# Agit_POVera_rev_3.net
KiCad netlist of a schematic drawn in EAGLE
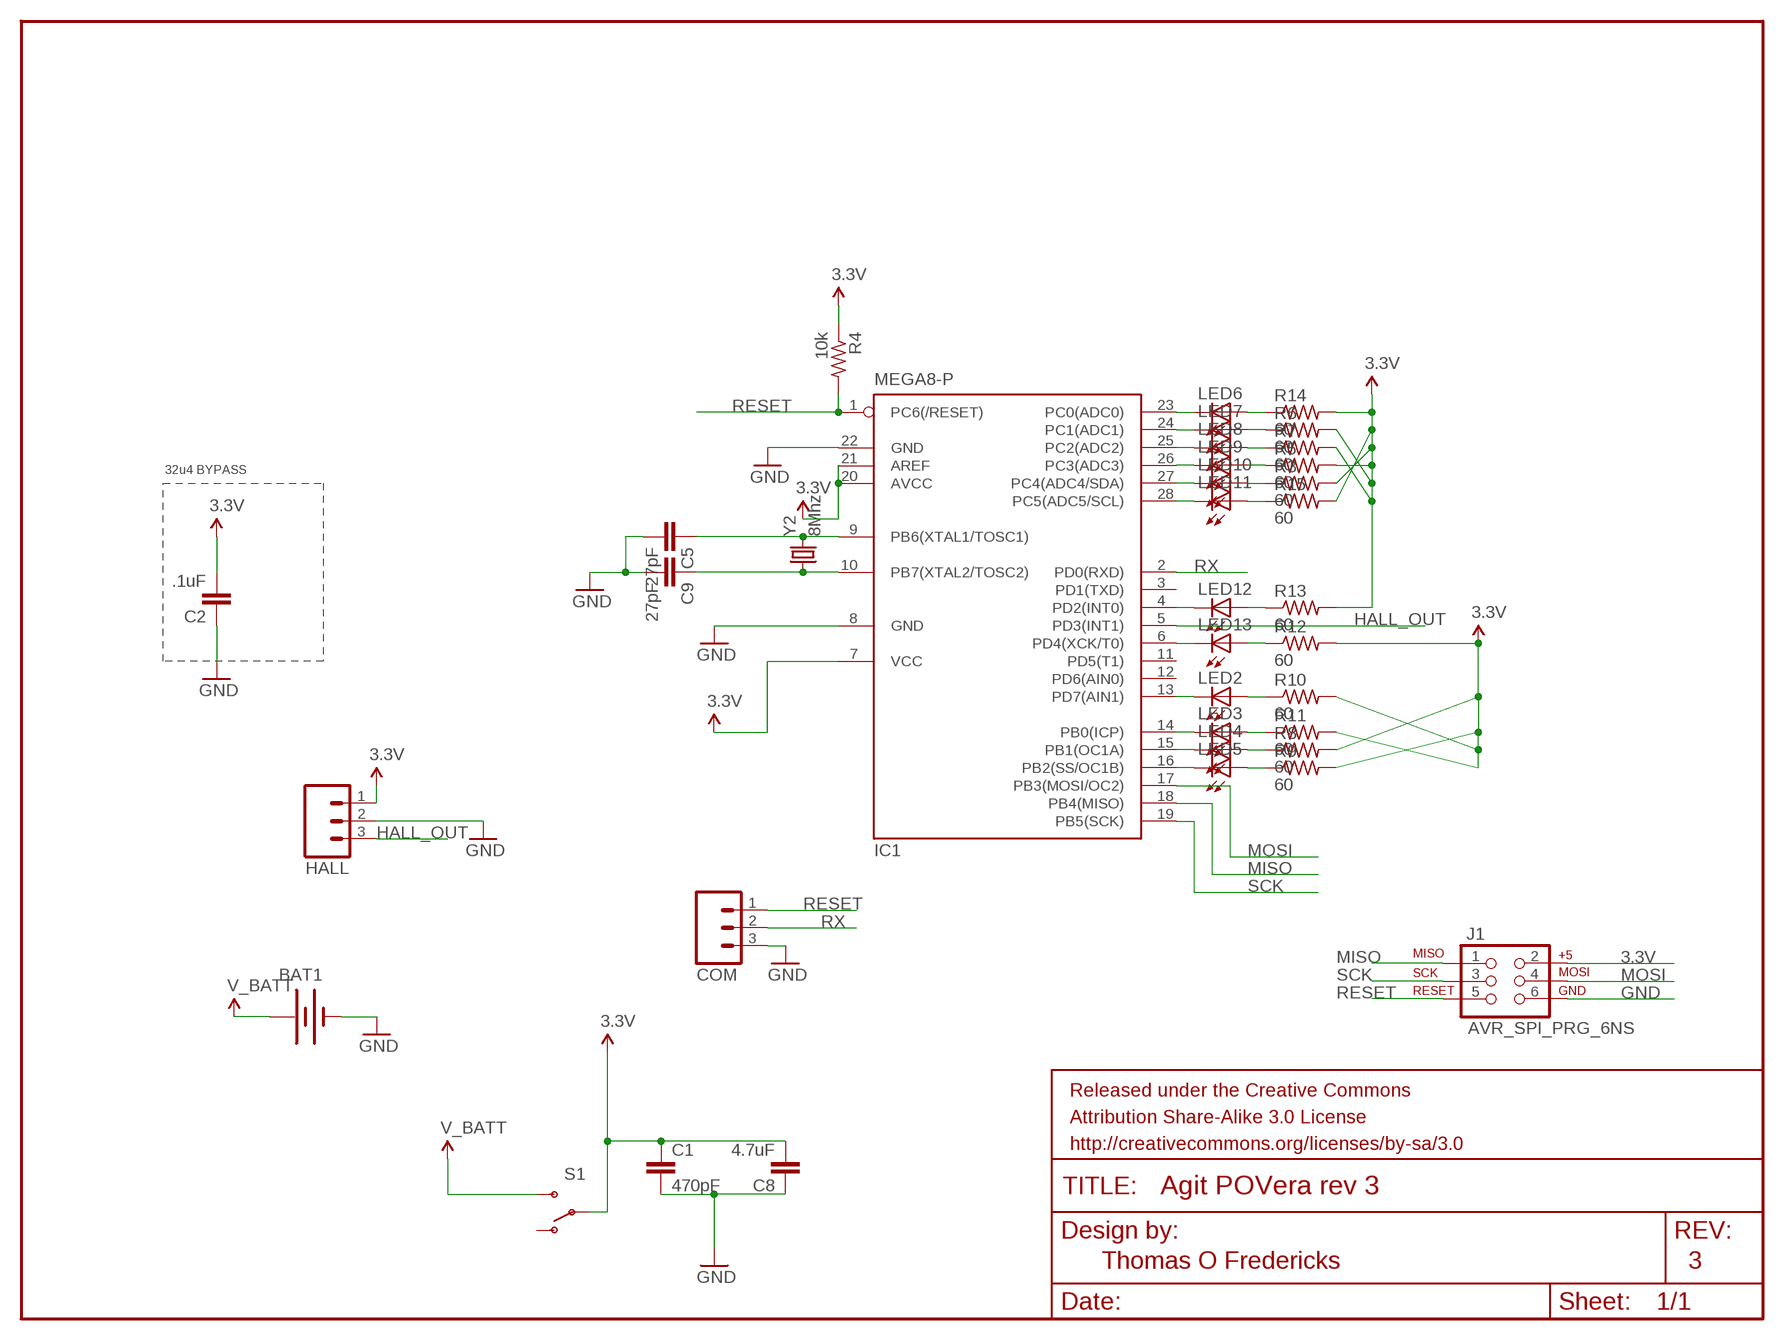
[diagram p0: schematic, sheet 1]

(export (version "E")
  (design (tool "Eeschema 10.0.6"))
  (components
    (comp (ref "BAT1")
      (value "BATTERY20PTH")
      (footprint "eagle-import:BATTCOM_20MM_PTH")
      (libsource (lib "eagle-import") (part "BATTERY20PTH"))
    )
    (comp (ref "C1")
      (value "470pF")
      (footprint "eagle-import:CAP-PTH-SMALLEZ")
      (libsource (lib "eagle-import") (part "CAPEZ"))
    )
    (comp (ref "C2")
      (value ".1uF")
      (footprint "eagle-import:CAP-PTH-SMALLEZ")
      (libsource (lib "eagle-import") (part "CAPEZ"))
    )
    (comp (ref "C5")
      (value "27pF")
      (footprint "eagle-import:CAP-PTH-SMALLEZ")
      (libsource (lib "eagle-import") (part "CAPEZ"))
    )
    (comp (ref "C8")
      (value "4.7uF")
      (footprint "eagle-import:CAP-PTH-SMALLEZ")
      (libsource (lib "eagle-import") (part "CAPEZ"))
    )
    (comp (ref "C9")
      (value "27pF")
      (footprint "eagle-import:CAP-PTH-SMALLEZ")
      (libsource (lib "eagle-import") (part "CAPEZ"))
    )
    (comp (ref "COM")
      (value "M03PTH")
      (footprint "eagle-import:1X03")
      (libsource (lib "eagle-import") (part "M03PTH"))
    )
    (comp (ref "HALL")
      (value "M03PTH")
      (footprint "eagle-import:1X03")
      (libsource (lib "eagle-import") (part "M03PTH"))
    )
    (comp (ref "IC1")
      (value "MEGA8-P")
      (footprint "eagle-import:DIL28-3")
      (libsource (lib "eagle-import") (part "MEGA8-P"))
    )
    (comp (ref "J1")
      (value "AVR_SPI_PRG_6NS")
      (footprint "eagle-import:2X3-NS")
      (libsource (lib "eagle-import") (part "AVR_SPI_PRG_6NS"))
    )
    (comp (ref "LED2")
      (value "LED5MM")
      (footprint "eagle-import:LED5MM")
      (libsource (lib "eagle-import") (part "LED5MM"))
    )
    (comp (ref "LED3")
      (value "LED5MM")
      (footprint "eagle-import:LED5MM")
      (libsource (lib "eagle-import") (part "LED5MM"))
    )
    (comp (ref "LED4")
      (value "LED5MM")
      (footprint "eagle-import:LED5MM")
      (libsource (lib "eagle-import") (part "LED5MM"))
    )
    (comp (ref "LED5")
      (value "LED5MM")
      (footprint "eagle-import:LED5MM")
      (libsource (lib "eagle-import") (part "LED5MM"))
    )
    (comp (ref "LED6")
      (value "LED5MM")
      (footprint "eagle-import:LED5MM")
      (libsource (lib "eagle-import") (part "LED5MM"))
    )
    (comp (ref "LED7")
      (value "LED5MM")
      (footprint "eagle-import:LED5MM")
      (libsource (lib "eagle-import") (part "LED5MM"))
    )
    (comp (ref "LED8")
      (value "LED5MM")
      (footprint "eagle-import:LED5MM")
      (libsource (lib "eagle-import") (part "LED5MM"))
    )
    (comp (ref "LED9")
      (value "LED5MM")
      (footprint "eagle-import:LED5MM")
      (libsource (lib "eagle-import") (part "LED5MM"))
    )
    (comp (ref "LED10")
      (value "LED5MM")
      (footprint "eagle-import:LED5MM")
      (libsource (lib "eagle-import") (part "LED5MM"))
    )
    (comp (ref "LED11")
      (value "LED5MM")
      (footprint "eagle-import:LED5MM")
      (libsource (lib "eagle-import") (part "LED5MM"))
    )
    (comp (ref "LED12")
      (value "LED5MM")
      (footprint "eagle-import:LED5MM")
      (libsource (lib "eagle-import") (part "LED5MM"))
    )
    (comp (ref "LED13")
      (value "LED5MM")
      (footprint "eagle-import:LED5MM")
      (libsource (lib "eagle-import") (part "LED5MM"))
    )
    (comp (ref "R3")
      (value "60")
      (footprint "eagle-import:0204_7")
      (libsource (lib "eagle-import") (part "R-US_0204/7"))
    )
    (comp (ref "R4")
      (value "10k")
      (footprint "eagle-import:0204_7")
      (libsource (lib "eagle-import") (part "R-US_0204/7"))
    )
    (comp (ref "R5")
      (value "60")
      (footprint "eagle-import:0204_7")
      (libsource (lib "eagle-import") (part "R-US_0204/7"))
    )
    (comp (ref "R6")
      (value "60")
      (footprint "eagle-import:0204_7")
      (libsource (lib "eagle-import") (part "R-US_0204/7"))
    )
    (comp (ref "R7")
      (value "60")
      (footprint "eagle-import:0204_7")
      (libsource (lib "eagle-import") (part "R-US_0204/7"))
    )
    (comp (ref "R8")
      (value "60")
      (footprint "eagle-import:0204_7")
      (libsource (lib "eagle-import") (part "R-US_0204/7"))
    )
    (comp (ref "R9")
      (value "60")
      (footprint "eagle-import:0204_7")
      (libsource (lib "eagle-import") (part "R-US_0204/7"))
    )
    (comp (ref "R10")
      (value "60")
      (footprint "eagle-import:0204_7")
      (libsource (lib "eagle-import") (part "R-US_0204/7"))
    )
    (comp (ref "R11")
      (value "60")
      (footprint "eagle-import:0204_7")
      (libsource (lib "eagle-import") (part "R-US_0204/7"))
    )
    (comp (ref "R12")
      (value "60")
      (footprint "eagle-import:0204_7")
      (libsource (lib "eagle-import") (part "R-US_0204/7"))
    )
    (comp (ref "R13")
      (value "60")
      (footprint "eagle-import:0204_7")
      (libsource (lib "eagle-import") (part "R-US_0204/7"))
    )
    (comp (ref "R14")
      (value "60")
      (footprint "eagle-import:0204_7")
      (libsource (lib "eagle-import") (part "R-US_0204/7"))
    )
    (comp (ref "R15")
      (value "60")
      (footprint "eagle-import:0204_7")
      (libsource (lib "eagle-import") (part "R-US_0204/7"))
    )
    (comp (ref "S1")
      (value "SWITCH-SPDTPTH")
      (footprint "eagle-import:SWITCH-SPDT")
      (libsource (lib "eagle-import") (part "SWITCH-SPDTPTH"))
    )
    (comp (ref "Y2")
      (value "8Mhz")
      (footprint "eagle-import:HC49US")
      (libsource (lib "eagle-import") (part "CRYSTALHC49US"))
    )
  )
  (nets
    (net (code "1") (name "/HALL_OUT") (class "Default")
      (node (ref "HALL") (pin "3") (pinfunction "3_3") (pintype "passive"))
      (node (ref "IC1") (pin "5") (pinfunction "PD3(INT1)_5") (pintype "bidirectional"))
    )
    (net (code "2") (name "/MISO") (class "Default")
      (node (ref "IC1") (pin "18") (pinfunction "PB4(MISO)_18") (pintype "bidirectional"))
      (node (ref "J1") (pin "1") (pinfunction "1_1") (pintype "passive"))
    )
    (net (code "3") (name "/MOSI") (class "Default")
      (node (ref "IC1") (pin "17") (pinfunction "PB3(MOSI/OC2)_17") (pintype "bidirectional"))
      (node (ref "J1") (pin "4") (pinfunction "4_4") (pintype "passive"))
    )
    (net (code "4") (name "/RESET") (class "Default")
      (node (ref "COM") (pin "1") (pinfunction "1_1") (pintype "passive"))
      (node (ref "IC1") (pin "1") (pinfunction "PC6(/RESET)_1") (pintype "bidirectional"))
      (node (ref "J1") (pin "5") (pinfunction "5_5") (pintype "passive"))
      (node (ref "R4") (pin "2") (pinfunction "2_2") (pintype "passive"))
    )
    (net (code "5") (name "/RX") (class "Default")
      (node (ref "COM") (pin "2") (pinfunction "2_2") (pintype "passive"))
      (node (ref "IC1") (pin "2") (pinfunction "PD0(RXD)_2") (pintype "bidirectional"))
    )
    (net (code "6") (name "/SCK") (class "Default")
      (node (ref "IC1") (pin "19") (pinfunction "PB5(SCK)_19") (pintype "bidirectional"))
      (node (ref "J1") (pin "3") (pinfunction "3_3") (pintype "passive"))
    )
    (net (code "7") (name "3.3V") (class "Default")
      (node (ref "C1") (pin "1") (pinfunction "1_1") (pintype "passive"))
      (node (ref "C2") (pin "2") (pinfunction "2_2") (pintype "passive"))
      (node (ref "C8") (pin "2") (pinfunction "2_2") (pintype "passive"))
      (node (ref "HALL") (pin "1") (pinfunction "1_1") (pintype "passive"))
      (node (ref "IC1") (pin "20") (pinfunction "AVCC_20") (pintype "power_in"))
      (node (ref "IC1") (pin "21") (pinfunction "AREF_21") (pintype "passive"))
      (node (ref "IC1") (pin "7") (pinfunction "VCC_7") (pintype "power_in"))
      (node (ref "J1") (pin "2") (pinfunction "2_2") (pintype "passive"))
      (node (ref "R10") (pin "2") (pinfunction "2_2") (pintype "passive"))
      (node (ref "R11") (pin "2") (pinfunction "2_2") (pintype "passive"))
      (node (ref "R12") (pin "2") (pinfunction "2_2") (pintype "passive"))
      (node (ref "R13") (pin "2") (pinfunction "2_2") (pintype "passive"))
      (node (ref "R14") (pin "2") (pinfunction "2_2") (pintype "passive"))
      (node (ref "R15") (pin "2") (pinfunction "2_2") (pintype "passive"))
      (node (ref "R3") (pin "2") (pinfunction "2_2") (pintype "passive"))
      (node (ref "R4") (pin "1") (pinfunction "1_1") (pintype "passive"))
      (node (ref "R5") (pin "2") (pinfunction "2_2") (pintype "passive"))
      (node (ref "R6") (pin "2") (pinfunction "2_2") (pintype "passive"))
      (node (ref "R7") (pin "2") (pinfunction "2_2") (pintype "passive"))
      (node (ref "R8") (pin "2") (pinfunction "2_2") (pintype "passive"))
      (node (ref "R9") (pin "2") (pinfunction "2_2") (pintype "passive"))
      (node (ref "S1") (pin "2") (pinfunction "P_2") (pintype "passive"))
    )
    (net (code "8") (name "GND") (class "Default")
      (node (ref "BAT1") (pin "2") (pinfunction "-_2") (pintype "power_in"))
      (node (ref "C1") (pin "2") (pinfunction "2_2") (pintype "passive"))
      (node (ref "C2") (pin "1") (pinfunction "1_1") (pintype "passive"))
      (node (ref "C5") (pin "2") (pinfunction "2_2") (pintype "passive"))
      (node (ref "C8") (pin "1") (pinfunction "1_1") (pintype "passive"))
      (node (ref "C9") (pin "2") (pinfunction "2_2") (pintype "passive"))
      (node (ref "COM") (pin "3") (pinfunction "3_3") (pintype "passive"))
      (node (ref "HALL") (pin "2") (pinfunction "2_2") (pintype "passive"))
      (node (ref "IC1") (pin "22") (pinfunction "GND_22") (pintype "power_in"))
      (node (ref "IC1") (pin "8") (pinfunction "GND_8") (pintype "power_in"))
      (node (ref "J1") (pin "6") (pinfunction "6_6") (pintype "passive"))
    )
    (net (code "9") (name "Net-(IC1-PB0(ICP))") (class "Default")
      (node (ref "IC1") (pin "14") (pinfunction "PB0(ICP)_14") (pintype "bidirectional"))
      (node (ref "LED3") (pin "K") (pinfunction "C_K") (pintype "passive"))
    )
    (net (code "10") (name "Net-(IC1-PB1(OC1A))") (class "Default")
      (node (ref "IC1") (pin "15") (pinfunction "PB1(OC1A)_15") (pintype "bidirectional"))
      (node (ref "LED4") (pin "K") (pinfunction "C_K") (pintype "passive"))
    )
    (net (code "11") (name "Net-(IC1-PB2(SS{slash}OC1B))") (class "Default")
      (node (ref "IC1") (pin "16") (pinfunction "PB2(SS/OC1B)_16") (pintype "bidirectional"))
      (node (ref "LED5") (pin "K") (pinfunction "C_K") (pintype "passive"))
    )
    (net (code "12") (name "Net-(IC1-PB6(XTAL1{slash}TOSC1))") (class "Default")
      (node (ref "C5") (pin "1") (pinfunction "1_1") (pintype "passive"))
      (node (ref "IC1") (pin "9") (pinfunction "PB6(XTAL1/TOSC1)_9") (pintype "bidirectional"))
      (node (ref "Y2") (pin "2") (pinfunction "2_2") (pintype "passive"))
    )
    (net (code "13") (name "Net-(IC1-PB7(XTAL2{slash}TOSC2))") (class "Default")
      (node (ref "C9") (pin "1") (pinfunction "1_1") (pintype "passive"))
      (node (ref "IC1") (pin "10") (pinfunction "PB7(XTAL2/TOSC2)_10") (pintype "bidirectional"))
      (node (ref "Y2") (pin "1") (pinfunction "1_1") (pintype "passive"))
    )
    (net (code "14") (name "Net-(IC1-PC0(ADC0))") (class "Default")
      (node (ref "IC1") (pin "23") (pinfunction "PC0(ADC0)_23") (pintype "bidirectional"))
      (node (ref "LED6") (pin "K") (pinfunction "C_K") (pintype "passive"))
    )
    (net (code "15") (name "Net-(IC1-PC1(ADC1))") (class "Default")
      (node (ref "IC1") (pin "24") (pinfunction "PC1(ADC1)_24") (pintype "bidirectional"))
      (node (ref "LED7") (pin "K") (pinfunction "C_K") (pintype "passive"))
    )
    (net (code "16") (name "Net-(IC1-PC2(ADC2))") (class "Default")
      (node (ref "IC1") (pin "25") (pinfunction "PC2(ADC2)_25") (pintype "bidirectional"))
      (node (ref "LED8") (pin "K") (pinfunction "C_K") (pintype "passive"))
    )
    (net (code "17") (name "Net-(IC1-PC3(ADC3))") (class "Default")
      (node (ref "IC1") (pin "26") (pinfunction "PC3(ADC3)_26") (pintype "bidirectional"))
      (node (ref "LED9") (pin "K") (pinfunction "C_K") (pintype "passive"))
    )
    (net (code "18") (name "Net-(IC1-PC4(ADC4{slash}SDA))") (class "Default")
      (node (ref "IC1") (pin "27") (pinfunction "PC4(ADC4/SDA)_27") (pintype "bidirectional"))
      (node (ref "LED10") (pin "K") (pinfunction "C_K") (pintype "passive"))
    )
    (net (code "19") (name "Net-(IC1-PC5(ADC5{slash}SCL))") (class "Default")
      (node (ref "IC1") (pin "28") (pinfunction "PC5(ADC5/SCL)_28") (pintype "bidirectional"))
      (node (ref "LED11") (pin "K") (pinfunction "C_K") (pintype "passive"))
    )
    (net (code "20") (name "Net-(IC1-PD2(INT0))") (class "Default")
      (node (ref "IC1") (pin "4") (pinfunction "PD2(INT0)_4") (pintype "bidirectional"))
      (node (ref "LED12") (pin "K") (pinfunction "C_K") (pintype "passive"))
    )
    (net (code "21") (name "Net-(IC1-PD4(XCK{slash}T0))") (class "Default")
      (node (ref "IC1") (pin "6") (pinfunction "PD4(XCK/T0)_6") (pintype "bidirectional"))
      (node (ref "LED13") (pin "K") (pinfunction "C_K") (pintype "passive"))
    )
    (net (code "22") (name "Net-(IC1-PD7(AIN1))") (class "Default")
      (node (ref "IC1") (pin "13") (pinfunction "PD7(AIN1)_13") (pintype "bidirectional"))
      (node (ref "LED2") (pin "K") (pinfunction "C_K") (pintype "passive"))
    )
    (net (code "23") (name "Net-(LED2-PadA)") (class "Default")
      (node (ref "LED2") (pin "A") (pinfunction "A_A") (pintype "passive"))
      (node (ref "R10") (pin "1") (pinfunction "1_1") (pintype "passive"))
    )
    (net (code "24") (name "Net-(LED3-PadA)") (class "Default")
      (node (ref "LED3") (pin "A") (pinfunction "A_A") (pintype "passive"))
      (node (ref "R11") (pin "1") (pinfunction "1_1") (pintype "passive"))
    )
    (net (code "25") (name "Net-(LED4-PadA)") (class "Default")
      (node (ref "LED4") (pin "A") (pinfunction "A_A") (pintype "passive"))
      (node (ref "R8") (pin "1") (pinfunction "1_1") (pintype "passive"))
    )
    (net (code "26") (name "Net-(LED5-PadA)") (class "Default")
      (node (ref "LED5") (pin "A") (pinfunction "A_A") (pintype "passive"))
      (node (ref "R9") (pin "1") (pinfunction "1_1") (pintype "passive"))
    )
    (net (code "27") (name "Net-(LED6-PadA)") (class "Default")
      (node (ref "LED6") (pin "A") (pinfunction "A_A") (pintype "passive"))
      (node (ref "R14") (pin "1") (pinfunction "1_1") (pintype "passive"))
    )
    (net (code "28") (name "Net-(LED7-PadA)") (class "Default")
      (node (ref "LED7") (pin "A") (pinfunction "A_A") (pintype "passive"))
      (node (ref "R6") (pin "1") (pinfunction "1_1") (pintype "passive"))
    )
    (net (code "29") (name "Net-(LED8-PadA)") (class "Default")
      (node (ref "LED8") (pin "A") (pinfunction "A_A") (pintype "passive"))
      (node (ref "R7") (pin "1") (pinfunction "1_1") (pintype "passive"))
    )
    (net (code "30") (name "Net-(LED9-PadA)") (class "Default")
      (node (ref "LED9") (pin "A") (pinfunction "A_A") (pintype "passive"))
      (node (ref "R5") (pin "1") (pinfunction "1_1") (pintype "passive"))
    )
    (net (code "31") (name "Net-(LED10-PadA)") (class "Default")
      (node (ref "LED10") (pin "A") (pinfunction "A_A") (pintype "passive"))
      (node (ref "R3") (pin "1") (pinfunction "1_1") (pintype "passive"))
    )
    (net (code "32") (name "Net-(LED11-PadA)") (class "Default")
      (node (ref "LED11") (pin "A") (pinfunction "A_A") (pintype "passive"))
      (node (ref "R15") (pin "1") (pinfunction "1_1") (pintype "passive"))
    )
    (net (code "33") (name "Net-(LED12-PadA)") (class "Default")
      (node (ref "LED12") (pin "A") (pinfunction "A_A") (pintype "passive"))
      (node (ref "R13") (pin "1") (pinfunction "1_1") (pintype "passive"))
    )
    (net (code "34") (name "Net-(LED13-PadA)") (class "Default")
      (node (ref "LED13") (pin "A") (pinfunction "A_A") (pintype "passive"))
      (node (ref "R12") (pin "1") (pinfunction "1_1") (pintype "passive"))
    )
    (net (code "35") (name "V_BATT") (class "Default")
      (node (ref "BAT1") (pin "1") (pinfunction "+_1") (pintype "power_in"))
      (node (ref "S1") (pin "3") (pinfunction "S_3") (pintype "passive"))
    )
    (net (code "36") (name "unconnected-(IC1-PD1(TXD)-Pad3)") (class "Default")
      (node (ref "IC1") (pin "3") (pinfunction "PD1(TXD)_3") (pintype "bidirectional"))
    )
    (net (code "37") (name "unconnected-(IC1-PD5(T1)-Pad11)") (class "Default")
      (node (ref "IC1") (pin "11") (pinfunction "PD5(T1)_11") (pintype "bidirectional"))
    )
    (net (code "38") (name "unconnected-(IC1-PD6(AIN0)-Pad12)") (class "Default")
      (node (ref "IC1") (pin "12") (pinfunction "PD6(AIN0)_12") (pintype "bidirectional"))
    )
    (net (code "39") (name "unconnected-(S1-O-Pad1)") (class "Default")
      (node (ref "S1") (pin "1") (pinfunction "O_1") (pintype "passive"))
    )
  )
)
